# motion.net
KiCad netlist of a schematic drawn in EAGLE
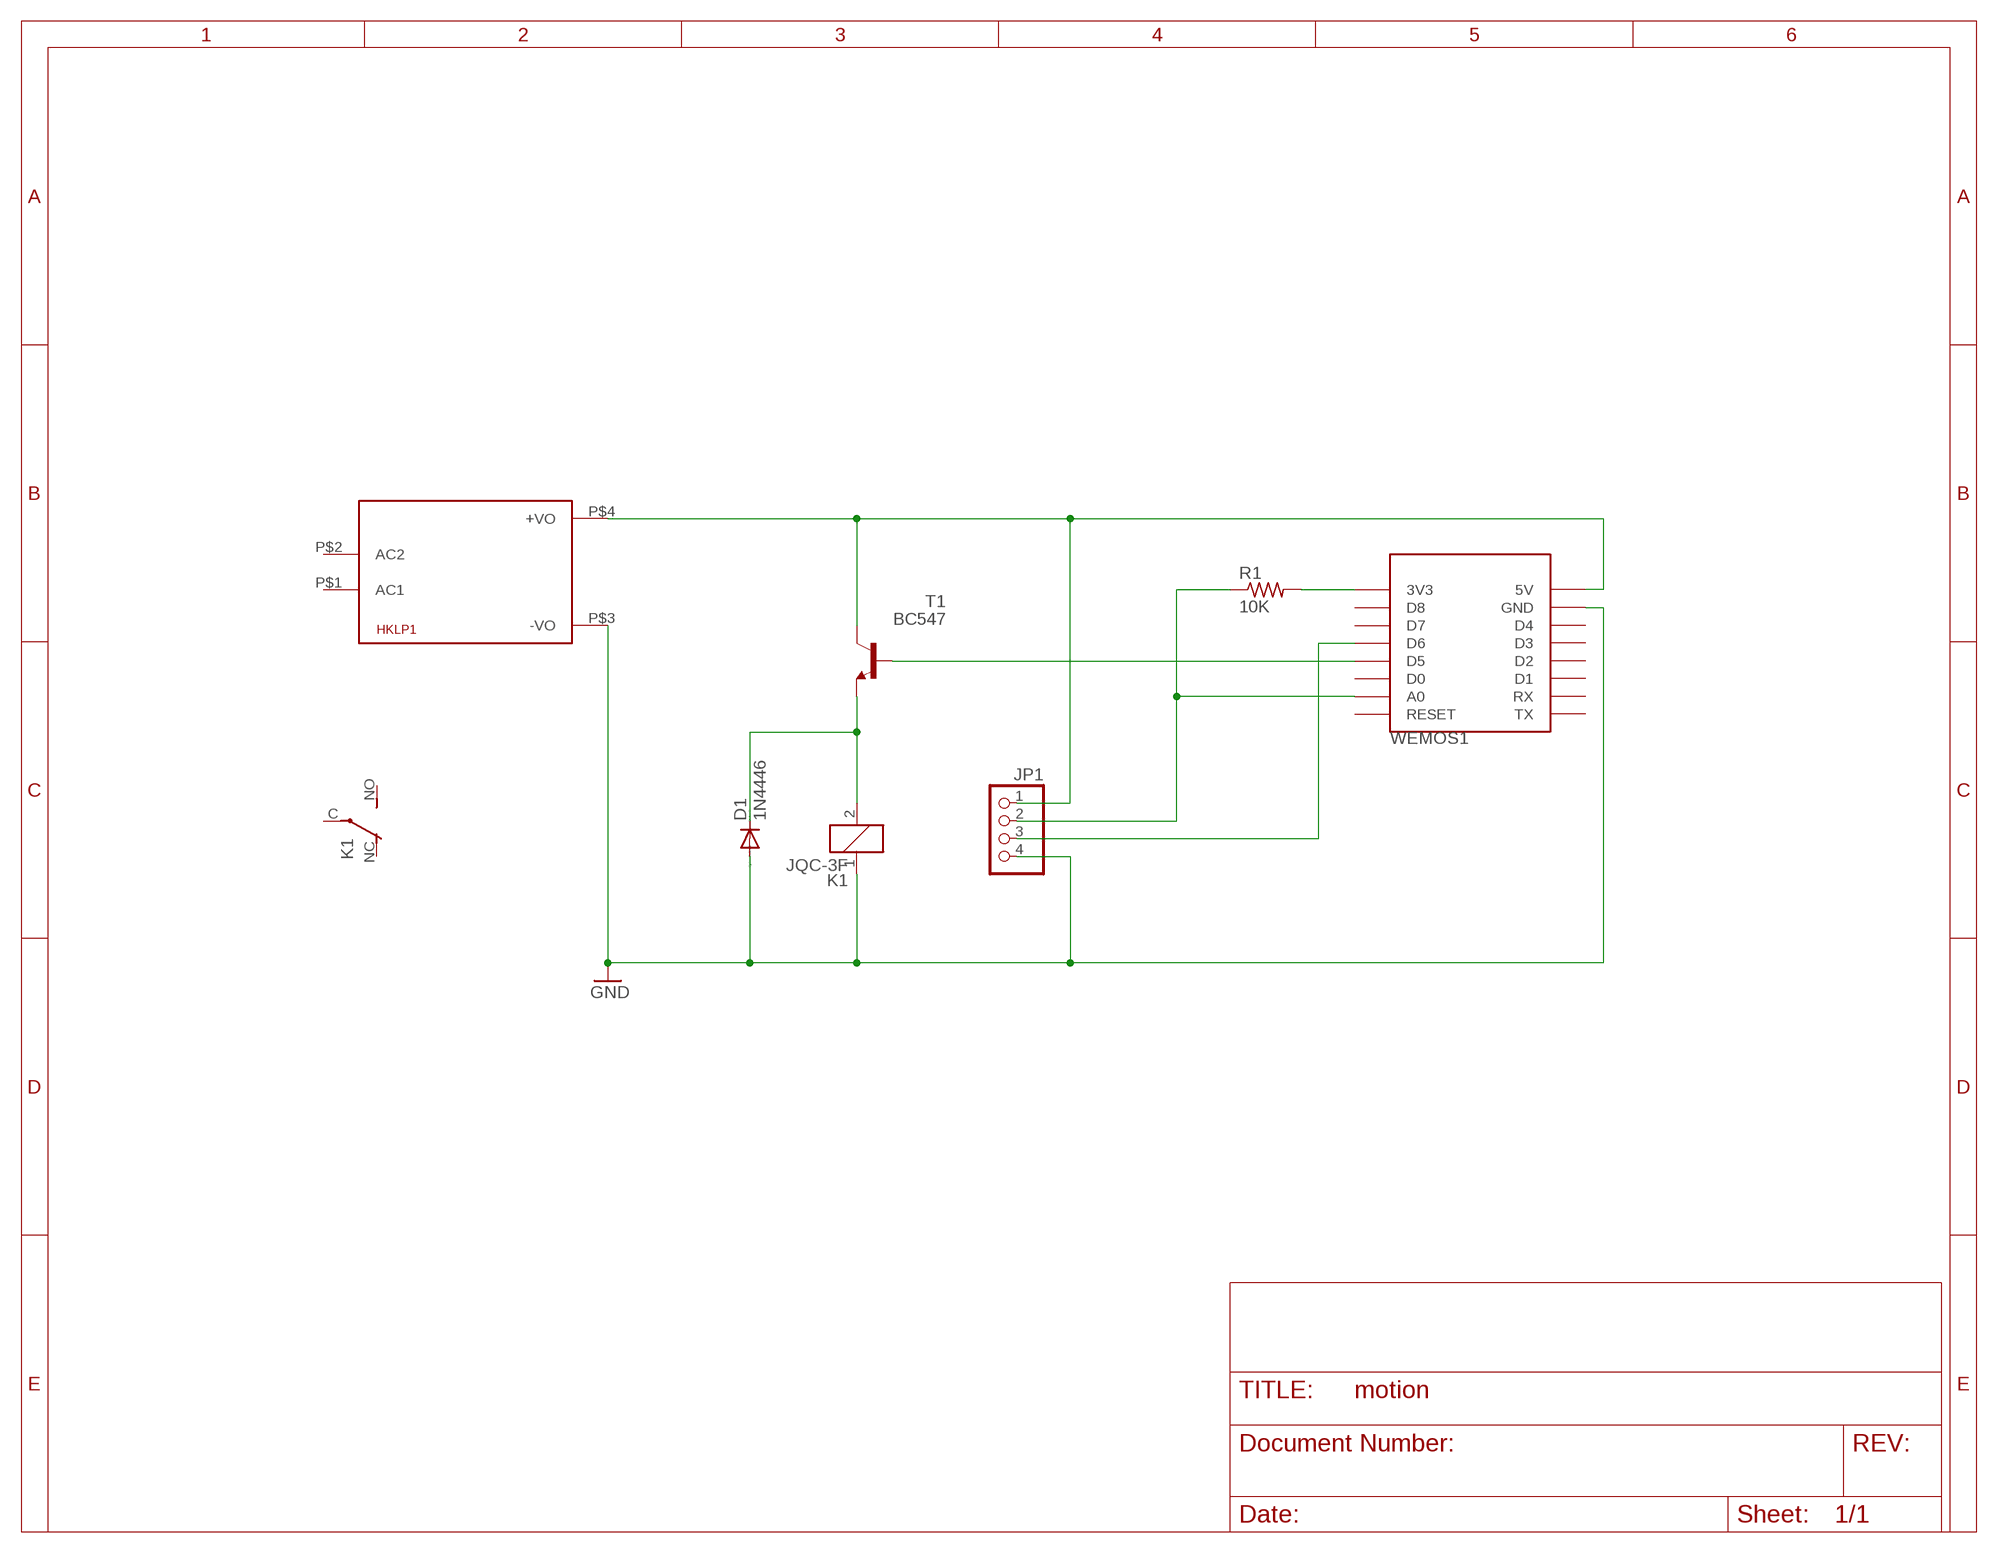
[diagram p0: schematic, sheet 1]

(export (version "E")
  (design (tool "Eeschema 10.0.6"))
  (components
    (comp (ref "D1")
      (value "1N4446")
      (footprint "eagle-import:DO35-10")
      (libsource (lib "eagle-import") (part "1N4446"))
    )
    (comp (ref "HKLP1")
      (value "HKLPM01")
      (footprint "eagle-import:HKLPM01")
      (libsource (lib "eagle-import") (part "HKLPM01"))
    )
    (comp (ref "JP1")
      (value "PINHD-1X4")
      (footprint "eagle-import:1X04")
      (libsource (lib "eagle-import") (part "PINHD-1X4"))
    )
    (comp (ref "K1")
      (value "JQC-3F")
      (footprint "eagle-import:JS-M")
      (libsource (lib "eagle-import") (part "JS-M1-9V-4"))
    )
    (comp (ref "R1")
      (value "10K")
      (footprint "eagle-import:0309V")
      (libsource (lib "eagle-import") (part "R-US_0309/V"))
    )
    (comp (ref "T1")
      (value "BC547")
      (footprint "eagle-import:TO92")
      (libsource (lib "eagle-import") (part "BC547"))
    )
    (comp (ref "WEMOS1")
      (value "WEMOS-D1-MINI")
      (footprint "eagle-import:WEMOS-D1-MINI")
      (libsource (lib "eagle-import") (part "WEMOS-D1-MINI"))
    )
  )
  (nets
    (net (code "1") (name "GND") (class "Default")
      (node (ref "D1") (pin "A") (pinfunction "A_A") (pintype "passive"))
      (node (ref "HKLP1") (pin "P$3") (pinfunction "-VO_P$3") (pintype "bidirectional"))
      (node (ref "JP1") (pin "4") (pinfunction "4_4") (pintype "passive"))
      (node (ref "K1") (pin "1") (pinfunction "1_1") (pintype "passive"))
      (node (ref "WEMOS1") (pin "GND") (pinfunction "GND_GND") (pintype "bidirectional"))
    )
    (net (code "2") (name "Net-(HKLP1-+VO)") (class "Default")
      (node (ref "HKLP1") (pin "P$4") (pinfunction "+VO_P$4") (pintype "bidirectional"))
      (node (ref "JP1") (pin "1") (pinfunction "1_1") (pintype "passive"))
      (node (ref "T1") (pin "3") (pinfunction "C_3") (pintype "passive"))
      (node (ref "WEMOS1") (pin "5V") (pinfunction "5V_5V") (pintype "bidirectional"))
    )
    (net (code "3") (name "Net-(JP1-Pad2)") (class "Default")
      (node (ref "JP1") (pin "2") (pinfunction "2_2") (pintype "passive"))
      (node (ref "R1") (pin "1") (pinfunction "1_1") (pintype "passive"))
      (node (ref "WEMOS1") (pin "A0") (pinfunction "A0_A0") (pintype "bidirectional"))
    )
    (net (code "4") (name "Net-(JP1-Pad3)") (class "Default")
      (node (ref "JP1") (pin "3") (pinfunction "3_3") (pintype "passive"))
      (node (ref "WEMOS1") (pin "D6") (pinfunction "D6_D6") (pintype "bidirectional"))
    )
    (net (code "5") (name "Net-(R1-Pad2)") (class "Default")
      (node (ref "R1") (pin "2") (pinfunction "2_2") (pintype "passive"))
      (node (ref "WEMOS1") (pin "3V3") (pinfunction "3V3_3V3") (pintype "bidirectional"))
    )
    (net (code "6") (name "Net-(T1-B)") (class "Default")
      (node (ref "T1") (pin "2") (pinfunction "B_2") (pintype "passive"))
      (node (ref "WEMOS1") (pin "D5") (pinfunction "D5_D5") (pintype "bidirectional"))
    )
    (net (code "7") (name "Net-(T1-E)") (class "Default")
      (node (ref "D1") (pin "C") (pinfunction "C_C") (pintype "passive"))
      (node (ref "K1") (pin "2") (pinfunction "2_2") (pintype "passive"))
      (node (ref "T1") (pin "1") (pinfunction "E_1") (pintype "passive"))
    )
    (net (code "8") (name "unconnected-(HKLP1-AC1-PadP$1)") (class "Default")
      (node (ref "HKLP1") (pin "P$1") (pinfunction "AC1_P$1") (pintype "bidirectional"))
    )
    (net (code "9") (name "unconnected-(HKLP1-AC2-PadP$2)") (class "Default")
      (node (ref "HKLP1") (pin "P$2") (pinfunction "AC2_P$2") (pintype "bidirectional"))
    )
    (net (code "10") (name "unconnected-(K1B-O-PadNC)") (class "Default")
      (node (ref "K1") (pin "NC") (pinfunction "O_NC") (pintype "passive"))
    )
    (net (code "11") (name "unconnected-(K1B-P-PadC)") (class "Default")
      (node (ref "K1") (pin "C") (pinfunction "P_C") (pintype "passive"))
    )
    (net (code "12") (name "unconnected-(K1B-S-PadNO)") (class "Default")
      (node (ref "K1") (pin "NO") (pinfunction "S_NO") (pintype "passive"))
    )
    (net (code "13") (name "unconnected-(WEMOS1-PadD0)") (class "Default")
      (node (ref "WEMOS1") (pin "D0") (pinfunction "D0_D0") (pintype "bidirectional"))
    )
    (net (code "14") (name "unconnected-(WEMOS1-PadD1)") (class "Default")
      (node (ref "WEMOS1") (pin "D1") (pinfunction "D1_D1") (pintype "bidirectional"))
    )
    (net (code "15") (name "unconnected-(WEMOS1-PadD2)") (class "Default")
      (node (ref "WEMOS1") (pin "D2") (pinfunction "D2_D2") (pintype "bidirectional"))
    )
    (net (code "16") (name "unconnected-(WEMOS1-PadD3)") (class "Default")
      (node (ref "WEMOS1") (pin "D3") (pinfunction "D3_D3") (pintype "bidirectional"))
    )
    (net (code "17") (name "unconnected-(WEMOS1-PadD4)") (class "Default")
      (node (ref "WEMOS1") (pin "D4") (pinfunction "D4_D4") (pintype "bidirectional"))
    )
    (net (code "18") (name "unconnected-(WEMOS1-PadD7)") (class "Default")
      (node (ref "WEMOS1") (pin "D7") (pinfunction "D7_D7") (pintype "bidirectional"))
    )
    (net (code "19") (name "unconnected-(WEMOS1-PadD8)") (class "Default")
      (node (ref "WEMOS1") (pin "D8") (pinfunction "D8_D8") (pintype "bidirectional"))
    )
    (net (code "20") (name "unconnected-(WEMOS1-PadRESET)") (class "Default")
      (node (ref "WEMOS1") (pin "RESET") (pinfunction "RESET_RESET") (pintype "bidirectional"))
    )
    (net (code "21") (name "unconnected-(WEMOS1-PadRX)") (class "Default")
      (node (ref "WEMOS1") (pin "RX") (pinfunction "RX_RX") (pintype "bidirectional"))
    )
    (net (code "22") (name "unconnected-(WEMOS1-PadTX)") (class "Default")
      (node (ref "WEMOS1") (pin "TX") (pinfunction "TX_TX") (pintype "bidirectional"))
    )
  )
)
